# controlador_temperatura.net
KiCad netlist of a schematic drawn in EAGLE
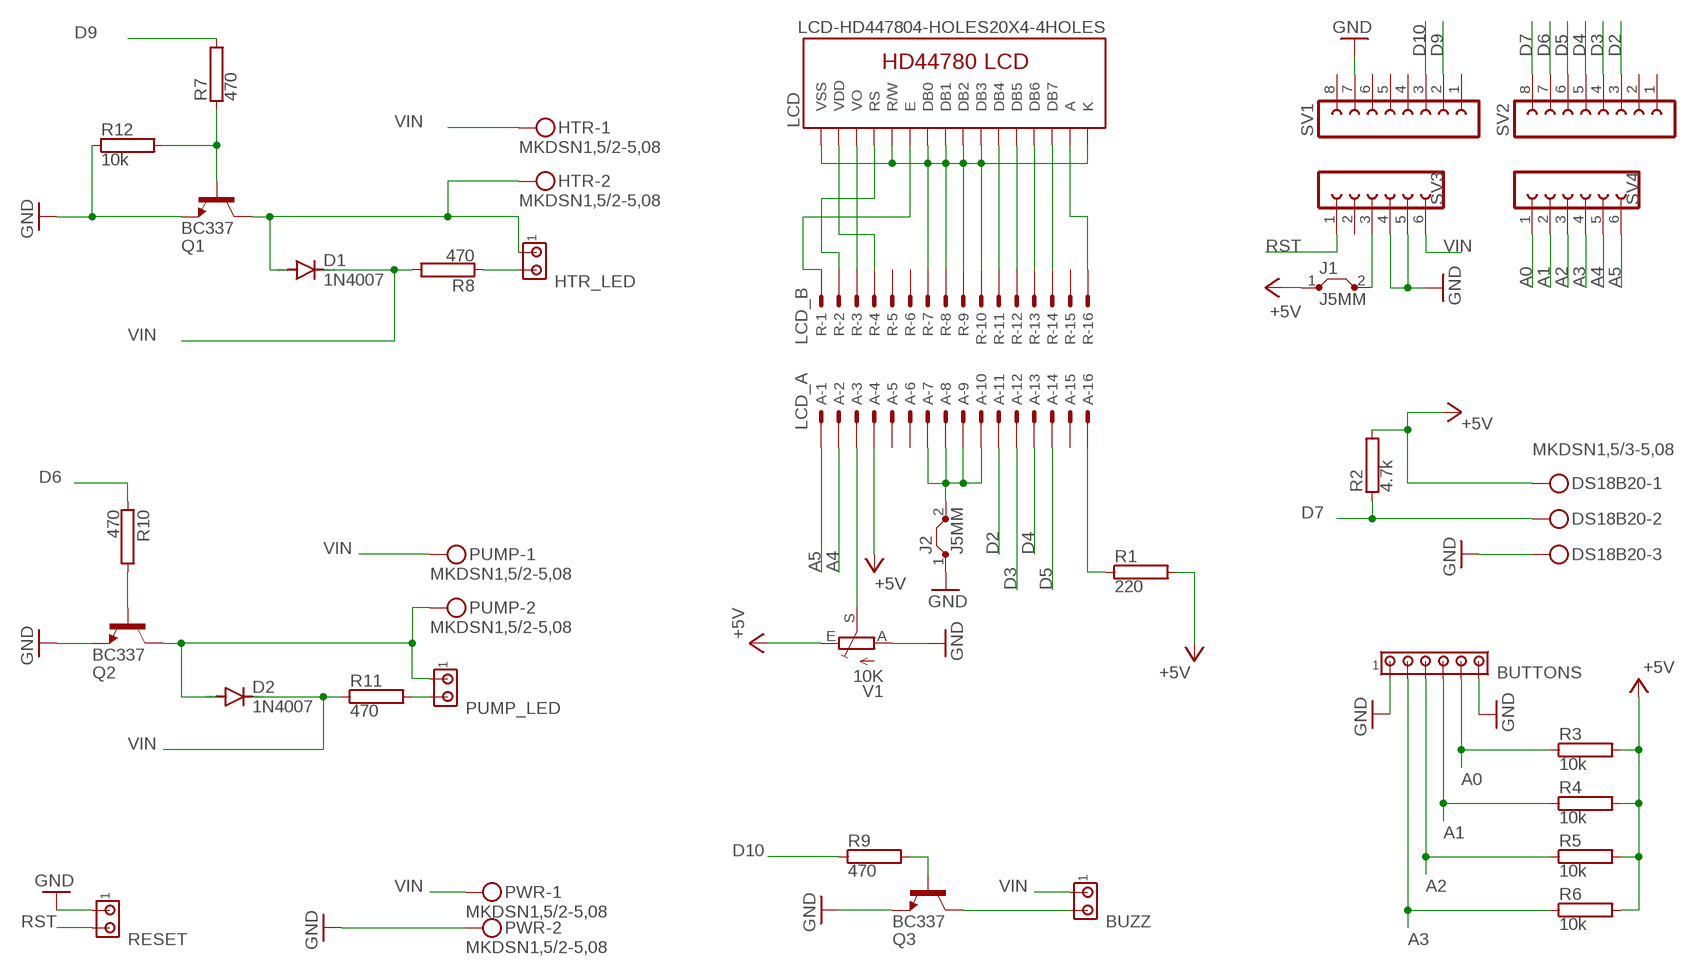
[diagram p0: schematic, sheet 1]

(export (version "E")
  (design (tool "Eeschema 10.0.6"))
  (components
    (comp (ref "A")
      (value "LCD_A")
      (footprint "eagle-import:057-016-1")
      (libsource (lib "eagle-import") (part "057-016-1"))
    )
    (comp (ref "BUTTONS")
      (value "MTA06-100")
      (footprint "eagle-import:10X06MTA")
      (libsource (lib "eagle-import") (part "MTA06-100"))
    )
    (comp (ref "BUZZ")
      (value "MTA02-100")
      (footprint "eagle-import:10X02MTA")
      (libsource (lib "eagle-import") (part "MTA02-100"))
    )
    (comp (ref "D1")
      (value "1N4007")
      (footprint "eagle-import:DO41-10")
      (libsource (lib "eagle-import") (part "1N4004"))
    )
    (comp (ref "D2")
      (value "1N4007")
      (footprint "eagle-import:DO41-10")
      (libsource (lib "eagle-import") (part "1N4004"))
    )
    (comp (ref "DS18B20")
      (value "MKDSN1,5/3-5,08")
      (footprint "eagle-import:MKDSN1,5_3-5,08")
      (libsource (lib "eagle-import") (part "MKDSN1,5/3-5,08"))
    )
    (comp (ref "HTR")
      (value "MKDSN1,5/2-5,08")
      (footprint "eagle-import:MKDSN1,5_2-5,08")
      (libsource (lib "eagle-import") (part "MKDSN1,5/2-5,08"))
    )
    (comp (ref "HTR_LED")
      (value "MTA02-100")
      (footprint "eagle-import:10X02MTA")
      (libsource (lib "eagle-import") (part "MTA02-100"))
    )
    (comp (ref "J1")
      (value "J5MM")
      (footprint "eagle-import:05")
      (libsource (lib "eagle-import") (part "J5MM"))
    )
    (comp (ref "J2")
      (value "J5MM")
      (footprint "eagle-import:05")
      (libsource (lib "eagle-import") (part "J5MM"))
    )
    (comp (ref "LCD")
      (value "LCD-HD447804-HOLES20X4-4HOLES")
      (footprint "eagle-import:LCD-20X4-4HOLES")
      (libsource (lib "eagle-import") (part "LCD-HD4478020X4-4HOLES4-HOLES"))
    )
    (comp (ref "PUMP")
      (value "MKDSN1,5/2-5,08")
      (footprint "eagle-import:MKDSN1,5_2-5,08")
      (libsource (lib "eagle-import") (part "MKDSN1,5/2-5,08"))
    )
    (comp (ref "PUMP_LED")
      (value "MTA02-100")
      (footprint "eagle-import:10X02MTA")
      (libsource (lib "eagle-import") (part "MTA02-100"))
    )
    (comp (ref "PWR")
      (value "MKDSN1,5/2-5,08")
      (footprint "eagle-import:MKDSN1,5_2-5,08")
      (libsource (lib "eagle-import") (part "MKDSN1,5/2-5,08"))
    )
    (comp (ref "Q1")
      (value "BC337")
      (footprint "eagle-import:TO92")
      (libsource (lib "eagle-import") (part "BC337"))
    )
    (comp (ref "Q2")
      (value "BC337")
      (footprint "eagle-import:TO92")
      (libsource (lib "eagle-import") (part "BC337"))
    )
    (comp (ref "Q3")
      (value "BC337")
      (footprint "eagle-import:TO92")
      (libsource (lib "eagle-import") (part "BC337"))
    )
    (comp (ref "R")
      (value "LCD_B")
      (footprint "eagle-import:057-016-1")
      (libsource (lib "eagle-import") (part "057-016-1"))
    )
    (comp (ref "R1")
      (value "220")
      (footprint "eagle-import:RS1_8")
      (libsource (lib "eagle-import") (part "RRS1/8"))
    )
    (comp (ref "R2")
      (value "4.7k")
      (footprint "eagle-import:RS1_8")
      (libsource (lib "eagle-import") (part "RRS1/8"))
    )
    (comp (ref "R3")
      (value "10k")
      (footprint "eagle-import:RS1_8")
      (libsource (lib "eagle-import") (part "RRS1/8"))
    )
    (comp (ref "R4")
      (value "10k")
      (footprint "eagle-import:RS1_8")
      (libsource (lib "eagle-import") (part "RRS1/8"))
    )
    (comp (ref "R5")
      (value "10k")
      (footprint "eagle-import:RS1_8")
      (libsource (lib "eagle-import") (part "RRS1/8"))
    )
    (comp (ref "R6")
      (value "10k")
      (footprint "eagle-import:RS1_8")
      (libsource (lib "eagle-import") (part "RRS1/8"))
    )
    (comp (ref "R7")
      (value "470")
      (footprint "eagle-import:RS1_8")
      (libsource (lib "eagle-import") (part "RRS1/8"))
    )
    (comp (ref "R8")
      (value "470")
      (footprint "eagle-import:RS1_8")
      (libsource (lib "eagle-import") (part "RRS1/8"))
    )
    (comp (ref "R9")
      (value "470")
      (footprint "eagle-import:RS1_8")
      (libsource (lib "eagle-import") (part "RRS1/8"))
    )
    (comp (ref "R10")
      (value "470")
      (footprint "eagle-import:RS1_8")
      (libsource (lib "eagle-import") (part "RRS1/8"))
    )
    (comp (ref "R11")
      (value "470")
      (footprint "eagle-import:RS1_8")
      (libsource (lib "eagle-import") (part "RRS1/8"))
    )
    (comp (ref "R12")
      (value "10k")
      (footprint "eagle-import:RS1_8")
      (libsource (lib "eagle-import") (part "RRS1/8"))
    )
    (comp (ref "RESET")
      (value "MTA02-100")
      (footprint "eagle-import:10X02MTA")
      (libsource (lib "eagle-import") (part "MTA02-100"))
    )
    (comp (ref "SV1")
      (value "FE08-1")
      (footprint "eagle-import:FE08")
      (libsource (lib "eagle-import") (part "FE08-1"))
    )
    (comp (ref "SV2")
      (value "FE08-1")
      (footprint "eagle-import:FE08")
      (libsource (lib "eagle-import") (part "FE08-1"))
    )
    (comp (ref "SV3")
      (value "FE06-1")
      (footprint "eagle-import:FE06")
      (libsource (lib "eagle-import") (part "FE06-1"))
    )
    (comp (ref "SV4")
      (value "FE06-1")
      (footprint "eagle-import:FE06")
      (libsource (lib "eagle-import") (part "FE06-1"))
    )
    (comp (ref "V1")
      (value "10K")
      (footprint "eagle-import:B25P")
      (libsource (lib "eagle-import") (part "TRIM_EU-B25P"))
    )
  )
  (nets
    (net (code "1") (name "+5V") (class "Default")
      (node (ref "A") (pin "4") (pinfunction "S_4") (pintype "passive"))
      (node (ref "DS18B20") (pin "1") (pinfunction "KL_1") (pintype "passive"))
      (node (ref "J1") (pin "1") (pinfunction "1_1") (pintype "passive"))
      (node (ref "J1") (pin "2") (pinfunction "2_2") (pintype "passive"))
      (node (ref "R1") (pin "2") (pinfunction "2_2") (pintype "passive"))
      (node (ref "R2") (pin "2") (pinfunction "2_2") (pintype "passive"))
      (node (ref "R3") (pin "2") (pinfunction "2_2") (pintype "passive"))
      (node (ref "R4") (pin "2") (pinfunction "2_2") (pintype "passive"))
      (node (ref "R5") (pin "2") (pinfunction "2_2") (pintype "passive"))
      (node (ref "R6") (pin "2") (pinfunction "2_2") (pintype "passive"))
      (node (ref "SV3") (pin "3") (pinfunction "3_3") (pintype "passive"))
      (node (ref "V1") (pin "E") (pinfunction "E_E") (pintype "passive"))
    )
    (net (code "2") (name "/A0") (class "Default")
      (node (ref "BUTTONS") (pin "5") (pinfunction "5_5") (pintype "passive"))
      (node (ref "R3") (pin "1") (pinfunction "1_1") (pintype "passive"))
      (node (ref "SV4") (pin "1") (pinfunction "1_1") (pintype "passive"))
    )
    (net (code "3") (name "/A1") (class "Default")
      (node (ref "BUTTONS") (pin "4") (pinfunction "4_4") (pintype "passive"))
      (node (ref "R4") (pin "1") (pinfunction "1_1") (pintype "passive"))
      (node (ref "SV4") (pin "2") (pinfunction "2_2") (pintype "passive"))
    )
    (net (code "4") (name "/A2") (class "Default")
      (node (ref "BUTTONS") (pin "3") (pinfunction "3_3") (pintype "passive"))
      (node (ref "R5") (pin "1") (pinfunction "1_1") (pintype "passive"))
      (node (ref "SV4") (pin "3") (pinfunction "3_3") (pintype "passive"))
    )
    (net (code "5") (name "/A3") (class "Default")
      (node (ref "BUTTONS") (pin "2") (pinfunction "2_2") (pintype "passive"))
      (node (ref "R6") (pin "1") (pinfunction "1_1") (pintype "passive"))
      (node (ref "SV4") (pin "4") (pinfunction "4_4") (pintype "passive"))
    )
    (net (code "6") (name "/A4") (class "Default")
      (node (ref "A") (pin "2") (pinfunction "S_2") (pintype "passive"))
      (node (ref "SV4") (pin "5") (pinfunction "5_5") (pintype "passive"))
    )
    (net (code "7") (name "/A5") (class "Default")
      (node (ref "A") (pin "1") (pinfunction "S_1") (pintype "passive"))
      (node (ref "SV4") (pin "6") (pinfunction "6_6") (pintype "passive"))
    )
    (net (code "8") (name "/D2") (class "Default")
      (node (ref "A") (pin "11") (pinfunction "S_11") (pintype "passive"))
      (node (ref "SV2") (pin "3") (pinfunction "3_3") (pintype "passive"))
    )
    (net (code "9") (name "/D3") (class "Default")
      (node (ref "A") (pin "12") (pinfunction "S_12") (pintype "passive"))
      (node (ref "SV2") (pin "4") (pinfunction "4_4") (pintype "passive"))
    )
    (net (code "10") (name "/D4") (class "Default")
      (node (ref "A") (pin "13") (pinfunction "S_13") (pintype "passive"))
      (node (ref "SV2") (pin "5") (pinfunction "5_5") (pintype "passive"))
    )
    (net (code "11") (name "/D5") (class "Default")
      (node (ref "A") (pin "14") (pinfunction "S_14") (pintype "passive"))
      (node (ref "SV2") (pin "6") (pinfunction "6_6") (pintype "passive"))
    )
    (net (code "12") (name "/D6") (class "Default")
      (node (ref "R10") (pin "1") (pinfunction "1_1") (pintype "passive"))
      (node (ref "SV2") (pin "7") (pinfunction "7_7") (pintype "passive"))
    )
    (net (code "13") (name "/D7") (class "Default")
      (node (ref "DS18B20") (pin "2") (pinfunction "KL_2") (pintype "passive"))
      (node (ref "R2") (pin "1") (pinfunction "1_1") (pintype "passive"))
      (node (ref "SV2") (pin "8") (pinfunction "8_8") (pintype "passive"))
    )
    (net (code "14") (name "/D9") (class "Default")
      (node (ref "R7") (pin "2") (pinfunction "2_2") (pintype "passive"))
      (node (ref "SV1") (pin "2") (pinfunction "2_2") (pintype "passive"))
    )
    (net (code "15") (name "/D10") (class "Default")
      (node (ref "R9") (pin "1") (pinfunction "1_1") (pintype "passive"))
      (node (ref "SV1") (pin "3") (pinfunction "3_3") (pintype "passive"))
    )
    (net (code "16") (name "/RST") (class "Default")
      (node (ref "RESET") (pin "2") (pinfunction "2_2") (pintype "passive"))
      (node (ref "SV3") (pin "1") (pinfunction "1_1") (pintype "passive"))
    )
    (net (code "17") (name "/VIN") (class "Default")
      (node (ref "BUZZ") (pin "1") (pinfunction "1_1") (pintype "passive"))
      (node (ref "D1") (pin "C") (pinfunction "C_C") (pintype "passive"))
      (node (ref "D2") (pin "C") (pinfunction "C_C") (pintype "passive"))
      (node (ref "HTR") (pin "1") (pinfunction "KL_1") (pintype "passive"))
      (node (ref "PUMP") (pin "1") (pinfunction "KL_1") (pintype "passive"))
      (node (ref "PWR") (pin "1") (pinfunction "KL_1") (pintype "passive"))
      (node (ref "R11") (pin "1") (pinfunction "1_1") (pintype "passive"))
      (node (ref "R8") (pin "2") (pinfunction "2_2") (pintype "passive"))
      (node (ref "SV3") (pin "6") (pinfunction "6_6") (pintype "passive"))
    )
    (net (code "18") (name "GND") (class "Default")
      (node (ref "A") (pin "10") (pinfunction "S_10") (pintype "passive"))
      (node (ref "A") (pin "7") (pinfunction "S_7") (pintype "passive"))
      (node (ref "A") (pin "8") (pinfunction "S_8") (pintype "passive"))
      (node (ref "A") (pin "9") (pinfunction "S_9") (pintype "passive"))
      (node (ref "BUTTONS") (pin "1") (pinfunction "1_1") (pintype "passive"))
      (node (ref "BUTTONS") (pin "6") (pinfunction "6_6") (pintype "passive"))
      (node (ref "DS18B20") (pin "3") (pinfunction "KL_3") (pintype "passive"))
      (node (ref "J2") (pin "1") (pinfunction "1_1") (pintype "passive"))
      (node (ref "J2") (pin "2") (pinfunction "2_2") (pintype "passive"))
      (node (ref "PWR") (pin "2") (pinfunction "KL_2") (pintype "passive"))
      (node (ref "Q1") (pin "1") (pinfunction "E_1") (pintype "passive"))
      (node (ref "Q2") (pin "1") (pinfunction "E_1") (pintype "passive"))
      (node (ref "Q3") (pin "1") (pinfunction "E_1") (pintype "passive"))
      (node (ref "R12") (pin "1") (pinfunction "1_1") (pintype "passive"))
      (node (ref "RESET") (pin "1") (pinfunction "1_1") (pintype "passive"))
      (node (ref "SV1") (pin "7") (pinfunction "7_7") (pintype "passive"))
      (node (ref "SV3") (pin "4") (pinfunction "4_4") (pintype "passive"))
      (node (ref "SV3") (pin "5") (pinfunction "5_5") (pintype "passive"))
      (node (ref "V1") (pin "A") (pinfunction "A_A") (pintype "passive"))
    )
    (net (code "19") (name "Net-(AH-S)") (class "Default")
      (node (ref "A") (pin "16") (pinfunction "S_16") (pintype "passive"))
      (node (ref "R1") (pin "1") (pinfunction "1_1") (pintype "passive"))
    )
    (net (code "20") (name "Net-(AJ-S)") (class "Default")
      (node (ref "A") (pin "3") (pinfunction "S_3") (pintype "passive"))
      (node (ref "V1") (pin "S") (pinfunction "S_S") (pintype "passive"))
    )
    (net (code "21") (name "Net-(HTRB-KL)") (class "Default")
      (node (ref "D1") (pin "A") (pinfunction "A_A") (pintype "passive"))
      (node (ref "HTR") (pin "2") (pinfunction "KL_2") (pintype "passive"))
      (node (ref "HTR_LED") (pin "1") (pinfunction "1_1") (pintype "passive"))
      (node (ref "Q1") (pin "3") (pinfunction "C_3") (pintype "passive"))
    )
    (net (code "22") (name "Net-(HTR_LED-Pad2)") (class "Default")
      (node (ref "HTR_LED") (pin "2") (pinfunction "2_2") (pintype "passive"))
      (node (ref "R8") (pin "1") (pinfunction "1_1") (pintype "passive"))
    )
    (net (code "23") (name "Net-(LCD-A)") (class "Default")
      (node (ref "LCD") (pin "P$15") (pinfunction "A_P$15") (pintype "power_in"))
      (node (ref "R") (pin "16") (pinfunction "S_16") (pintype "passive"))
    )
    (net (code "24") (name "Net-(LCD-DB0)") (class "Default")
      (node (ref "LCD") (pin "P$1") (pinfunction "VSS_P$1") (pintype "power_in"))
      (node (ref "LCD") (pin "P$10") (pinfunction "DB3_P$10") (pintype "bidirectional"))
      (node (ref "LCD") (pin "P$16") (pinfunction "K_P$16") (pintype "power_in"))
      (node (ref "LCD") (pin "P$5") (pinfunction "R/W_P$5") (pintype "input"))
      (node (ref "LCD") (pin "P$7") (pinfunction "DB0_P$7") (pintype "bidirectional"))
      (node (ref "LCD") (pin "P$8") (pinfunction "DB1_P$8") (pintype "bidirectional"))
      (node (ref "LCD") (pin "P$9") (pinfunction "DB2_P$9") (pintype "bidirectional"))
      (node (ref "R") (pin "10") (pinfunction "S_10") (pintype "passive"))
      (node (ref "R") (pin "7") (pinfunction "S_7") (pintype "passive"))
      (node (ref "R") (pin "8") (pinfunction "S_8") (pintype "passive"))
      (node (ref "R") (pin "9") (pinfunction "S_9") (pintype "passive"))
    )
    (net (code "25") (name "Net-(LCD-DB4)") (class "Default")
      (node (ref "LCD") (pin "P$11") (pinfunction "DB4_P$11") (pintype "bidirectional"))
      (node (ref "R") (pin "11") (pinfunction "S_11") (pintype "passive"))
    )
    (net (code "26") (name "Net-(LCD-DB5)") (class "Default")
      (node (ref "LCD") (pin "P$12") (pinfunction "DB5_P$12") (pintype "bidirectional"))
      (node (ref "R") (pin "12") (pinfunction "S_12") (pintype "passive"))
    )
    (net (code "27") (name "Net-(LCD-DB6)") (class "Default")
      (node (ref "LCD") (pin "P$13") (pinfunction "DB6_P$13") (pintype "bidirectional"))
      (node (ref "R") (pin "13") (pinfunction "S_13") (pintype "passive"))
    )
    (net (code "28") (name "Net-(LCD-DB7)") (class "Default")
      (node (ref "LCD") (pin "P$14") (pinfunction "DB7_P$14") (pintype "bidirectional"))
      (node (ref "R") (pin "14") (pinfunction "S_14") (pintype "passive"))
    )
    (net (code "29") (name "Net-(LCD-E)") (class "Default")
      (node (ref "LCD") (pin "P$6") (pinfunction "E_P$6") (pintype "input"))
      (node (ref "R") (pin "1") (pinfunction "S_1") (pintype "passive"))
    )
    (net (code "30") (name "Net-(LCD-RS)") (class "Default")
      (node (ref "LCD") (pin "P$4") (pinfunction "RS_P$4") (pintype "input"))
      (node (ref "R") (pin "2") (pinfunction "S_2") (pintype "passive"))
    )
    (net (code "31") (name "Net-(LCD-VDD)") (class "Default")
      (node (ref "LCD") (pin "P$2") (pinfunction "VDD_P$2") (pintype "power_in"))
      (node (ref "R") (pin "4") (pinfunction "S_4") (pintype "passive"))
    )
    (net (code "32") (name "Net-(LCD-VO)") (class "Default")
      (node (ref "LCD") (pin "P$3") (pinfunction "VO_P$3") (pintype "bidirectional"))
      (node (ref "R") (pin "3") (pinfunction "S_3") (pintype "passive"))
    )
    (net (code "33") (name "Net-(PUMPB-KL)") (class "Default")
      (node (ref "D2") (pin "A") (pinfunction "A_A") (pintype "passive"))
      (node (ref "PUMP") (pin "2") (pinfunction "KL_2") (pintype "passive"))
      (node (ref "PUMP_LED") (pin "1") (pinfunction "1_1") (pintype "passive"))
      (node (ref "Q2") (pin "3") (pinfunction "C_3") (pintype "passive"))
    )
    (net (code "34") (name "Net-(PUMP_LED-Pad2)") (class "Default")
      (node (ref "PUMP_LED") (pin "2") (pinfunction "2_2") (pintype "passive"))
      (node (ref "R11") (pin "2") (pinfunction "2_2") (pintype "passive"))
    )
    (net (code "35") (name "Net-(Q1-B)") (class "Default")
      (node (ref "Q1") (pin "2") (pinfunction "B_2") (pintype "passive"))
      (node (ref "R12") (pin "2") (pinfunction "2_2") (pintype "passive"))
      (node (ref "R7") (pin "1") (pinfunction "1_1") (pintype "passive"))
    )
    (net (code "36") (name "Net-(Q2-B)") (class "Default")
      (node (ref "Q2") (pin "2") (pinfunction "B_2") (pintype "passive"))
      (node (ref "R10") (pin "2") (pinfunction "2_2") (pintype "passive"))
    )
    (net (code "37") (name "Net-(Q3-B)") (class "Default")
      (node (ref "Q3") (pin "2") (pinfunction "B_2") (pintype "passive"))
      (node (ref "R9") (pin "2") (pinfunction "2_2") (pintype "passive"))
    )
    (net (code "38") (name "Net-(Q3-C)") (class "Default")
      (node (ref "BUZZ") (pin "2") (pinfunction "2_2") (pintype "passive"))
      (node (ref "Q3") (pin "3") (pinfunction "C_3") (pintype "passive"))
    )
    (net (code "39") (name "unconnected-(AG-S-Pad15)") (class "Default")
      (node (ref "A") (pin "15") (pinfunction "S_15") (pintype "passive"))
    )
    (net (code "40") (name "unconnected-(AL-S-Pad5)") (class "Default")
      (node (ref "A") (pin "5") (pinfunction "S_5") (pintype "passive"))
    )
    (net (code "41") (name "unconnected-(AM-S-Pad6)") (class "Default")
      (node (ref "A") (pin "6") (pinfunction "S_6") (pintype "passive"))
    )
    (net (code "42") (name "unconnected-(RG-S-Pad15)") (class "Default")
      (node (ref "R") (pin "15") (pinfunction "S_15") (pintype "passive"))
    )
    (net (code "43") (name "unconnected-(RL-S-Pad5)") (class "Default")
      (node (ref "R") (pin "5") (pinfunction "S_5") (pintype "passive"))
    )
    (net (code "44") (name "unconnected-(RM-S-Pad6)") (class "Default")
      (node (ref "R") (pin "6") (pinfunction "S_6") (pintype "passive"))
    )
    (net (code "45") (name "unconnected-(SV1-Pad1)") (class "Default")
      (node (ref "SV1") (pin "1") (pinfunction "1_1") (pintype "passive"))
    )
    (net (code "46") (name "unconnected-(SV1-Pad4)") (class "Default")
      (node (ref "SV1") (pin "4") (pinfunction "4_4") (pintype "passive"))
    )
    (net (code "47") (name "unconnected-(SV1-Pad5)") (class "Default")
      (node (ref "SV1") (pin "5") (pinfunction "5_5") (pintype "passive"))
    )
    (net (code "48") (name "unconnected-(SV1-Pad6)") (class "Default")
      (node (ref "SV1") (pin "6") (pinfunction "6_6") (pintype "passive"))
    )
    (net (code "49") (name "unconnected-(SV1-Pad8)") (class "Default")
      (node (ref "SV1") (pin "8") (pinfunction "8_8") (pintype "passive"))
    )
    (net (code "50") (name "unconnected-(SV2-Pad1)") (class "Default")
      (node (ref "SV2") (pin "1") (pinfunction "1_1") (pintype "passive"))
    )
    (net (code "51") (name "unconnected-(SV2-Pad2)") (class "Default")
      (node (ref "SV2") (pin "2") (pinfunction "2_2") (pintype "passive"))
    )
    (net (code "52") (name "unconnected-(SV3-Pad2)") (class "Default")
      (node (ref "SV3") (pin "2") (pinfunction "2_2") (pintype "passive"))
    )
  )
)
